# SmartLightHub.net
KiCad netlist of a schematic drawn in EasyEDA
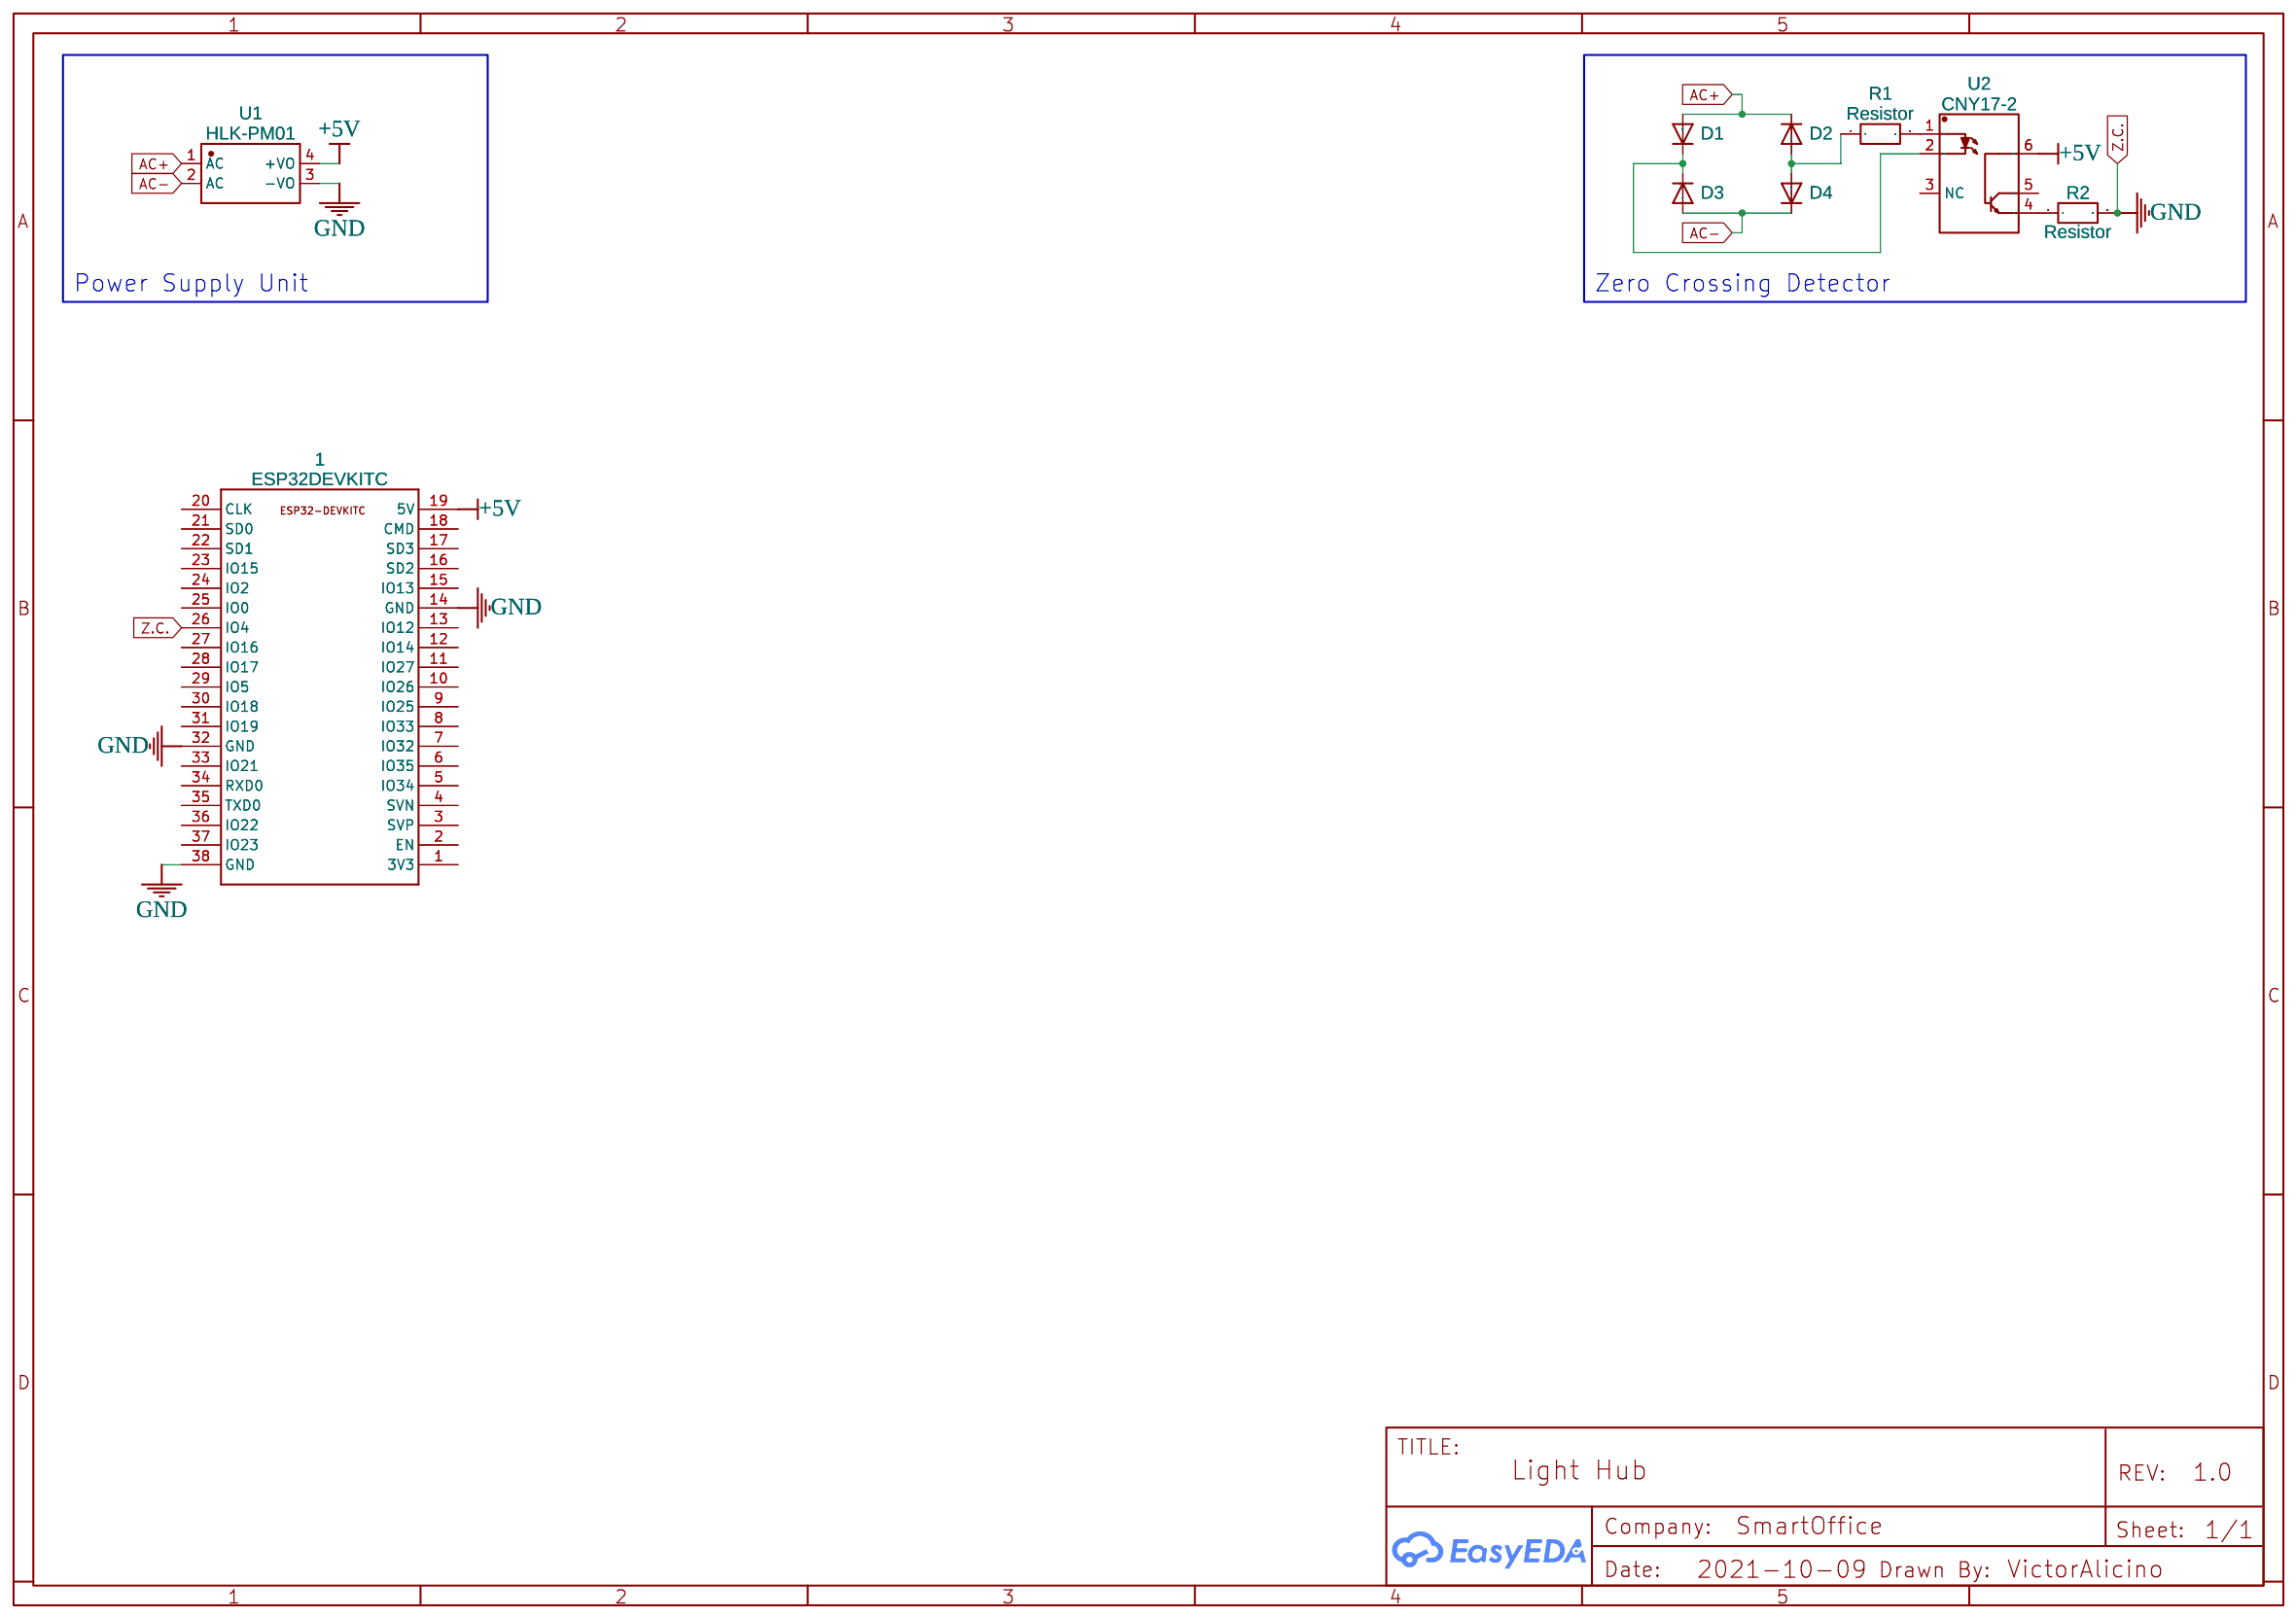
[diagram p0: schematic sheet]

(export (version "E")
  (design (tool "Eeschema 10.0.6"))
  (components
    (comp (ref "1") (value "ESP32DEVKITC") (libsource (lib "") (part "ESP32DEVKITC")))
    (comp (ref "D1") (value "DIODE") (libsource (lib "") (part "DIODE")))
    (comp (ref "D2") (value "DIODE") (libsource (lib "") (part "DIODE_1")))
    (comp (ref "D3") (value "DIODE") (libsource (lib "") (part "DIODE_1")))
    (comp (ref "D4") (value "DIODE") (libsource (lib "") (part "DIODE")))
    (comp (ref "R1") (value "Resistor") (libsource (lib "") (part "Resistor1_EU")))
    (comp (ref "R2") (value "Resistor") (libsource (lib "") (part "Resistor1_EU")))
    (comp (ref "U1")
      (value "HLK-PM01")
      (fields (field (name "BOM_Supplier Part") "C209903"))
      (libsource (lib "") (part "HLK-PM01"))
    )
    (comp (ref "U2")
      (value "CNY17-2")
      (fields (field (name "BOM_Supplier Part") "C10807"))
      (libsource (lib "") (part "CNY17-2"))
    )
  )
  (nets
    (net (code "1") (name "+5V") (class "Default")
      (node (ref "1") (pin "19") (pinfunction "5V_19") (pintype "bidirectional"))
      (node (ref "U1") (pin "4") (pinfunction "+VO_4") (pintype "unspecified"))
      (node (ref "U2") (pin "6") (pinfunction "BASE_6") (pintype "unspecified"))
    )
    (net (code "2") (name "AC+") (class "Default")
      (node (ref "D1") (pin "A") (pinfunction "A_A") (pintype "unspecified"))
      (node (ref "D2") (pin "C") (pinfunction "C_C") (pintype "unspecified"))
      (node (ref "U1") (pin "1") (pinfunction "AC_1") (pintype "unspecified"))
    )
    (net (code "3") (name "AC-") (class "Default")
      (node (ref "D3") (pin "A") (pinfunction "A_A") (pintype "unspecified"))
      (node (ref "D4") (pin "C") (pinfunction "C_C") (pintype "unspecified"))
      (node (ref "U1") (pin "2") (pinfunction "AC_2") (pintype "unspecified"))
    )
    (net (code "4") (name "Net-(D1-PadC)") (class "Default")
      (node (ref "D1") (pin "C") (pinfunction "C_C") (pintype "unspecified"))
      (node (ref "D3") (pin "C") (pinfunction "C_C") (pintype "unspecified"))
      (node (ref "U2") (pin "2") (pinfunction "2_2") (pintype "unspecified"))
    )
    (net (code "5") (name "Net-(D2-PadA)") (class "Default")
      (node (ref "D2") (pin "A") (pinfunction "A_A") (pintype "unspecified"))
      (node (ref "D4") (pin "A") (pinfunction "A_A") (pintype "unspecified"))
      (node (ref "R1") (pin "1") (pinfunction "1_1") (pintype "unspecified"))
    )
    (net (code "6") (name "Net-(R1-Pad2)") (class "Default")
      (node (ref "R1") (pin "2") (pinfunction "2_2") (pintype "unspecified"))
      (node (ref "U2") (pin "1") (pinfunction "1_1") (pintype "unspecified"))
    )
    (net (code "7") (name "Net-(U2-E)") (class "Default")
      (node (ref "R2") (pin "1") (pinfunction "1_1") (pintype "unspecified"))
      (node (ref "U2") (pin "4") (pinfunction "E_4") (pintype "unspecified"))
    )
    (net (code "8") (name "Z.C.") (class "Default")
      (node (ref "1") (pin "14") (pinfunction "GND_14") (pintype "bidirectional"))
      (node (ref "1") (pin "26") (pinfunction "IO4_26") (pintype "bidirectional"))
      (node (ref "1") (pin "32") (pinfunction "GND_32") (pintype "bidirectional"))
      (node (ref "1") (pin "38") (pinfunction "GND_38") (pintype "bidirectional"))
      (node (ref "R2") (pin "2") (pinfunction "2_2") (pintype "unspecified"))
      (node (ref "U1") (pin "3") (pinfunction "-VO_3") (pintype "unspecified"))
    )
    (net (code "9") (name "unconnected-(1-3V3-Pad1)") (class "Default")
      (node (ref "1") (pin "1") (pinfunction "3V3_1") (pintype "bidirectional"))
    )
    (net (code "10") (name "unconnected-(1-CLK-Pad20)") (class "Default")
      (node (ref "1") (pin "20") (pinfunction "CLK_20") (pintype "bidirectional"))
    )
    (net (code "11") (name "unconnected-(1-CMD-Pad18)") (class "Default")
      (node (ref "1") (pin "18") (pinfunction "CMD_18") (pintype "bidirectional"))
    )
    (net (code "12") (name "unconnected-(1-EN-Pad2)") (class "Default")
      (node (ref "1") (pin "2") (pinfunction "EN_2") (pintype "bidirectional"))
    )
    (net (code "13") (name "unconnected-(1-IO0-Pad25)") (class "Default")
      (node (ref "1") (pin "25") (pinfunction "IO0_25") (pintype "bidirectional"))
    )
    (net (code "14") (name "unconnected-(1-IO2-Pad24)") (class "Default")
      (node (ref "1") (pin "24") (pinfunction "IO2_24") (pintype "bidirectional"))
    )
    (net (code "15") (name "unconnected-(1-IO5-Pad29)") (class "Default")
      (node (ref "1") (pin "29") (pinfunction "IO5_29") (pintype "bidirectional"))
    )
    (net (code "16") (name "unconnected-(1-IO12-Pad13)") (class "Default")
      (node (ref "1") (pin "13") (pinfunction "IO12_13") (pintype "bidirectional"))
    )
    (net (code "17") (name "unconnected-(1-IO13-Pad15)") (class "Default")
      (node (ref "1") (pin "15") (pinfunction "IO13_15") (pintype "bidirectional"))
    )
    (net (code "18") (name "unconnected-(1-IO14-Pad12)") (class "Default")
      (node (ref "1") (pin "12") (pinfunction "IO14_12") (pintype "bidirectional"))
    )
    (net (code "19") (name "unconnected-(1-IO15-Pad23)") (class "Default")
      (node (ref "1") (pin "23") (pinfunction "IO15_23") (pintype "bidirectional"))
    )
    (net (code "20") (name "unconnected-(1-IO16-Pad27)") (class "Default")
      (node (ref "1") (pin "27") (pinfunction "IO16_27") (pintype "bidirectional"))
    )
    (net (code "21") (name "unconnected-(1-IO17-Pad28)") (class "Default")
      (node (ref "1") (pin "28") (pinfunction "IO17_28") (pintype "bidirectional"))
    )
    (net (code "22") (name "unconnected-(1-IO18-Pad30)") (class "Default")
      (node (ref "1") (pin "30") (pinfunction "IO18_30") (pintype "bidirectional"))
    )
    (net (code "23") (name "unconnected-(1-IO19-Pad31)") (class "Default")
      (node (ref "1") (pin "31") (pinfunction "IO19_31") (pintype "bidirectional"))
    )
    (net (code "24") (name "unconnected-(1-IO21-Pad33)") (class "Default")
      (node (ref "1") (pin "33") (pinfunction "IO21_33") (pintype "bidirectional"))
    )
    (net (code "25") (name "unconnected-(1-IO22-Pad36)") (class "Default")
      (node (ref "1") (pin "36") (pinfunction "IO22_36") (pintype "bidirectional"))
    )
    (net (code "26") (name "unconnected-(1-IO23-Pad37)") (class "Default")
      (node (ref "1") (pin "37") (pinfunction "IO23_37") (pintype "bidirectional"))
    )
    (net (code "27") (name "unconnected-(1-IO25-Pad9)") (class "Default")
      (node (ref "1") (pin "9") (pinfunction "IO25_9") (pintype "bidirectional"))
    )
    (net (code "28") (name "unconnected-(1-IO26-Pad10)") (class "Default")
      (node (ref "1") (pin "10") (pinfunction "IO26_10") (pintype "bidirectional"))
    )
    (net (code "29") (name "unconnected-(1-IO27-Pad11)") (class "Default")
      (node (ref "1") (pin "11") (pinfunction "IO27_11") (pintype "bidirectional"))
    )
    (net (code "30") (name "unconnected-(1-IO32-Pad7)") (class "Default")
      (node (ref "1") (pin "7") (pinfunction "IO32_7") (pintype "bidirectional"))
    )
    (net (code "31") (name "unconnected-(1-IO33-Pad8)") (class "Default")
      (node (ref "1") (pin "8") (pinfunction "IO33_8") (pintype "bidirectional"))
    )
    (net (code "32") (name "unconnected-(1-IO34-Pad5)") (class "Default")
      (node (ref "1") (pin "5") (pinfunction "IO34_5") (pintype "bidirectional"))
    )
    (net (code "33") (name "unconnected-(1-IO35-Pad6)") (class "Default")
      (node (ref "1") (pin "6") (pinfunction "IO35_6") (pintype "bidirectional"))
    )
    (net (code "34") (name "unconnected-(1-RXD0-Pad34)") (class "Default")
      (node (ref "1") (pin "34") (pinfunction "RXD0_34") (pintype "bidirectional"))
    )
    (net (code "35") (name "unconnected-(1-SD0-Pad21)") (class "Default")
      (node (ref "1") (pin "21") (pinfunction "SD0_21") (pintype "bidirectional"))
    )
    (net (code "36") (name "unconnected-(1-SD1-Pad22)") (class "Default")
      (node (ref "1") (pin "22") (pinfunction "SD1_22") (pintype "bidirectional"))
    )
    (net (code "37") (name "unconnected-(1-SD2-Pad16)") (class "Default")
      (node (ref "1") (pin "16") (pinfunction "SD2_16") (pintype "bidirectional"))
    )
    (net (code "38") (name "unconnected-(1-SD3-Pad17)") (class "Default")
      (node (ref "1") (pin "17") (pinfunction "SD3_17") (pintype "bidirectional"))
    )
    (net (code "39") (name "unconnected-(1-SVN-Pad4)") (class "Default")
      (node (ref "1") (pin "4") (pinfunction "SVN_4") (pintype "bidirectional"))
    )
    (net (code "40") (name "unconnected-(1-SVP-Pad3)") (class "Default")
      (node (ref "1") (pin "3") (pinfunction "SVP_3") (pintype "bidirectional"))
    )
    (net (code "41") (name "unconnected-(1-TXD0-Pad35)") (class "Default")
      (node (ref "1") (pin "35") (pinfunction "TXD0_35") (pintype "bidirectional"))
    )
    (net (code "42") (name "unconnected-(U2-C-Pad5)") (class "Default")
      (node (ref "U2") (pin "5") (pinfunction "C_5") (pintype "unspecified"))
    )
    (net (code "43") (name "unconnected-(U2-NC-Pad3)") (class "Default")
      (node (ref "U2") (pin "3") (pinfunction "NC_3") (pintype "unspecified"))
    )
  )
)
